# PIC32MK.net
KiCad netlist of a schematic drawn in Altium Designer
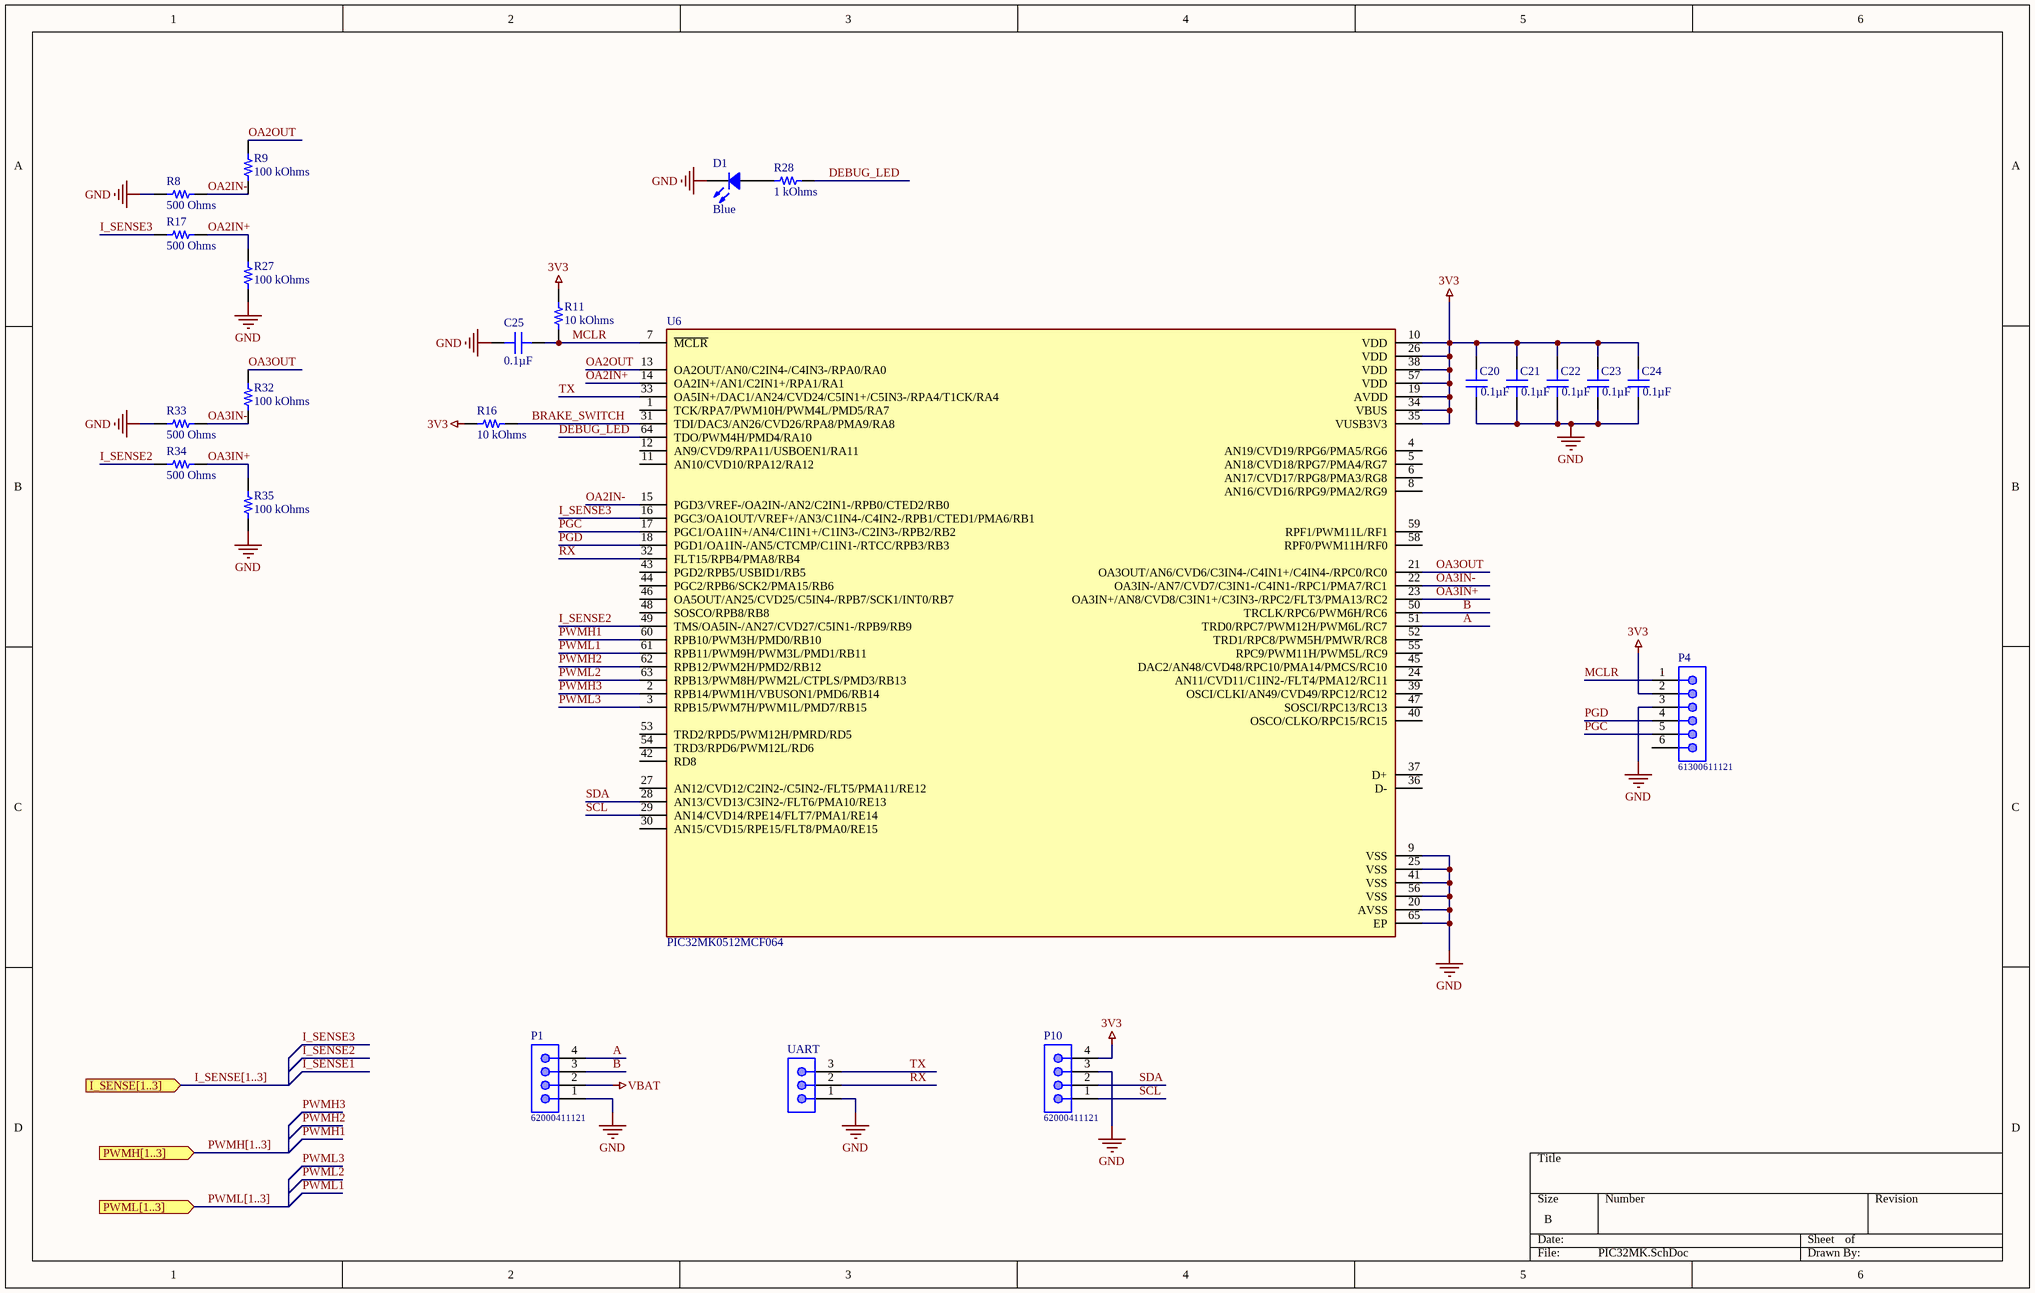
[diagram p0: PIC32MK.SchDoc]

(export (version "E")
  (design (tool "Eeschema 10.0.6"))
  (components
    (comp (ref "C20")
      (value "0.1µF")
      (footprint "CAP 0603_1608")
      (description "CAP CER 0.1UF 100V 0603 EPOXY")
      (fields
        (field (name "PART NUMBER") "GCG188R92A104KA03D")
        (field (name "MANUFACTURER") "Murata Electronics")
      )
      (libsource (lib "Celestial Altium Library - altium_library") (part "Capacitor"))
    )
    (comp (ref "C21")
      (value "0.1µF")
      (footprint "CAP 0603_1608")
      (description "CAP CER 0.1UF 100V 0603 EPOXY")
      (fields
        (field (name "PART NUMBER") "GCG188R92A104KA03D")
        (field (name "MANUFACTURER") "Murata Electronics")
      )
      (libsource (lib "Celestial Altium Library - altium_library") (part "Capacitor"))
    )
    (comp (ref "C22")
      (value "0.1µF")
      (footprint "CAP 0603_1608")
      (description "CAP CER 0.1UF 100V 0603 EPOXY")
      (fields
        (field (name "PART NUMBER") "GCG188R92A104KA03D")
        (field (name "MANUFACTURER") "Murata Electronics")
      )
      (libsource (lib "Celestial Altium Library - altium_library") (part "Capacitor"))
    )
    (comp (ref "C23")
      (value "0.1µF")
      (footprint "CAP 0603_1608")
      (description "CAP CER 0.1UF 100V 0603 EPOXY")
      (fields
        (field (name "PART NUMBER") "GCG188R92A104KA03D")
        (field (name "MANUFACTURER") "Murata Electronics")
      )
      (libsource (lib "Celestial Altium Library - altium_library") (part "Capacitor"))
    )
    (comp (ref "C24")
      (value "0.1µF")
      (footprint "CAP 0603_1608")
      (description "CAP CER 0.1UF 100V 0603 EPOXY")
      (fields
        (field (name "PART NUMBER") "GCG188R92A104KA03D")
        (field (name "MANUFACTURER") "Murata Electronics")
      )
      (libsource (lib "Celestial Altium Library - altium_library") (part "Capacitor"))
    )
    (comp (ref "C25")
      (value "0.1µF")
      (footprint "CAP 0603_1608")
      (description "CAP CER 0.1UF 100V 0603 EPOXY")
      (fields
        (field (name "PART NUMBER") "GCG188R92A104KA03D")
        (field (name "MANUFACTURER") "Murata Electronics")
      )
      (libsource (lib "Celestial Altium Library - altium_library") (part "Capacitor"))
    )
    (comp (ref "D1")
      (value "Blue")
      (footprint "LED 0603_1608 GREEN")
      (description "Blue LED")
      (fields (field (name "PART NUMBER") "XZCDGK53W-8VF") (field (name "MANUFACTURER") "SunLED"))
      (libsource (lib "Celestial Altium Library - altium_library") (part "LED"))
    )
    (comp (ref "P1")
      (value "62000411121")
      (footprint "62000411121")
      (description "WR-PHD Pin Header, THT, pitch 2mm, Single Row, Vertical, 4p")
      (fields (field (name "MANUFACTURER") "Wurth Elektronik"))
      (libsource (lib "Altium_WR-PHD") (part "62000411121"))
    )
    (comp (ref "P4")
      (value "61300611121")
      (footprint "61300611121")
      (description "WR-PHD Pin Header, THT, pitch 2.54mm, Single Row, Vertical, 6p")
      (fields (field (name "MANUFACTURER") "Wurth Elektronik"))
      (libsource (lib "Altium_WR-PHD") (part "61300611121"))
    )
    (comp (ref "P10")
      (value "62000411121")
      (footprint "62000411121")
      (description "WR-PHD Pin Header, THT, pitch 2mm, Single Row, Vertical, 4p")
      (fields (field (name "MANUFACTURER") "Wurth Elektronik"))
      (libsource (lib "Altium_WR-PHD") (part "62000411121"))
    )
    (comp (ref "R8")
      (value "500 Ohms")
      (footprint "RES 0603_1608")
      (description "RES SMD 500 OHM 0.05% 1/10W 0603")
      (fields (field (name "PART NUMBER") "TNPU0603500RAZEN00") (field (name "MANUFACTURER") "Vishay Dale"))
      (libsource (lib "Celestial Altium Library - altium_library") (part "Resistor"))
    )
    (comp (ref "R9")
      (value "100 kOhms")
      (footprint "RES 0603_1608")
      (description "RES SMD 100K OHM 1% 1/4W 0603")
      (fields (field (name "PART NUMBER") "RCA0603100KFKEAHP") (field (name "MANUFACTURER") "Vishay Dale"))
      (libsource (lib "Celestial Altium Library - altium_library") (part "Resistor"))
    )
    (comp (ref "R11")
      (value "10 kOhms")
      (footprint "RES 0603_1608")
      (description "RES 10K OHM 0.1% 1/16W 0603")
      (fields
        (field (name "PART NUMBER") "RNCS0603BKE10K0")
        (field (name "MANUFACTURER") "Stackpole Electronics Inc")
      )
      (libsource (lib "Celestial Altium Library - altium_library") (part "Resistor"))
    )
    (comp (ref "R16")
      (value "10 kOhms")
      (footprint "RES 0603_1608")
      (description "RES 10K OHM 0.1% 1/16W 0603")
      (fields
        (field (name "PART NUMBER") "RNCS0603BKE10K0")
        (field (name "MANUFACTURER") "Stackpole Electronics Inc")
      )
      (libsource (lib "Celestial Altium Library - altium_library") (part "Resistor"))
    )
    (comp (ref "R17")
      (value "500 Ohms")
      (footprint "RES 0603_1608")
      (description "RES SMD 500 OHM 0.05% 1/10W 0603")
      (fields (field (name "PART NUMBER") "TNPU0603500RAZEN00") (field (name "MANUFACTURER") "Vishay Dale"))
      (libsource (lib "Celestial Altium Library - altium_library") (part "Resistor"))
    )
    (comp (ref "R27")
      (value "100 kOhms")
      (footprint "RES 0603_1608")
      (description "RES SMD 100K OHM 1% 1/4W 0603")
      (fields (field (name "PART NUMBER") "RCA0603100KFKEAHP") (field (name "MANUFACTURER") "Vishay Dale"))
      (libsource (lib "Celestial Altium Library - altium_library") (part "Resistor"))
    )
    (comp (ref "R28")
      (value "1 kOhms")
      (footprint "RES 0603_1608")
      (description "RES 1K OHM 0.5% 1/10W 0603")
      (fields
        (field (name "PART NUMBER") "RNCF0603DTE1K00")
        (field (name "MANUFACTURER") "Stackpole Electronics Inc")
      )
      (libsource (lib "Celestial Altium Library - altium_library") (part "Resistor"))
    )
    (comp (ref "R32")
      (value "100 kOhms")
      (footprint "RES 0603_1608")
      (description "RES SMD 100K OHM 1% 1/4W 0603")
      (fields (field (name "PART NUMBER") "RCA0603100KFKEAHP") (field (name "MANUFACTURER") "Vishay Dale"))
      (libsource (lib "Celestial Altium Library - altium_library") (part "Resistor"))
    )
    (comp (ref "R33")
      (value "500 Ohms")
      (footprint "RES 0603_1608")
      (description "RES SMD 500 OHM 0.05% 1/10W 0603")
      (fields (field (name "PART NUMBER") "TNPU0603500RAZEN00") (field (name "MANUFACTURER") "Vishay Dale"))
      (libsource (lib "Celestial Altium Library - altium_library") (part "Resistor"))
    )
    (comp (ref "R34")
      (value "500 Ohms")
      (footprint "RES 0603_1608")
      (description "RES SMD 500 OHM 0.05% 1/10W 0603")
      (fields (field (name "PART NUMBER") "TNPU0603500RAZEN00") (field (name "MANUFACTURER") "Vishay Dale"))
      (libsource (lib "Celestial Altium Library - altium_library") (part "Resistor"))
    )
    (comp (ref "R35")
      (value "100 kOhms")
      (footprint "RES 0603_1608")
      (description "RES SMD 100K OHM 1% 1/4W 0603")
      (fields (field (name "PART NUMBER") "RCA0603100KFKEAHP") (field (name "MANUFACTURER") "Vishay Dale"))
      (libsource (lib "Celestial Altium Library - altium_library") (part "Resistor"))
    )
    (comp (ref "U6")
      (value "PIC32MK0512MCF064")
      (footprint "QFN50P900X900X100-65N")
      (description "PIC32MK Microcontroller IC 32-Bit 120MHz 1MB _1M x 8_ FLASH 64-TQFP _10x10_")
      (fields
        (field (name "MP") "PIC32MK1024MCF064-I/PT")
        (field (name "DIGI-KEY_PART_NUMBER") "PIC32MK1024MCF064-I/PT-ND")
      )
      (libsource (lib "IC") (part "PIC32MK0512MCF064"))
    )
    (comp (ref "UART")
      (value "3 pin 2mm JST Male")
      (footprint "3pin - 2mm header")
      (libsource (lib "IC") (part "3 pin 2mm JST Male"))
    )
  )
  (nets
    (net (code "1") (name "/A") (class "Default")
      (node (ref "P1") (pin "4") (pinfunction "4_4") (pintype "passive"))
      (node (ref "U6") (pin "51") (pinfunction "TRD0/RPC7/PWM12H/PWM6L/RC7_51") (pintype "passive"))
    )
    (net (code "2") (name "/B") (class "Default")
      (node (ref "P1") (pin "3") (pinfunction "3_3") (pintype "passive"))
      (node (ref "U6") (pin "50") (pinfunction "TRCLK/RPC6/PWM6H/RC6_50") (pintype "passive"))
    )
    (net (code "3") (name "/BRAKE_SWITCH") (class "Default")
      (node (ref "R16") (pin "1") (pinfunction "1_1") (pintype "passive"))
      (node (ref "U6") (pin "31") (pinfunction "TDI/DAC3/AN26/CVD26/RPA8/PMA9/RA8_31") (pintype "passive"))
    )
    (net (code "4") (name "/DEBUG_LED") (class "Default")
      (node (ref "R28") (pin "1") (pinfunction "1_1") (pintype "passive"))
      (node (ref "U6") (pin "64") (pinfunction "TDO/PWM4H/PMD4/RA10_64") (pintype "passive"))
    )
    (net (code "6") (name "/I_SENSE2") (class "Default")
      (node (ref "R34") (pin "1") (pinfunction "1_1") (pintype "passive"))
      (node (ref "U6") (pin "49") (pinfunction "TMS/OA5IN-/AN27/CVD27/C5IN1-/RPB9/RB9_49") (pintype "passive"))
    )
    (net (code "7") (name "/I_SENSE3") (class "Default")
      (node (ref "R17") (pin "1") (pinfunction "1_1") (pintype "passive"))
      (node (ref "U6") (pin "16") (pinfunction "PGC3/OA1OUT/VREF+/AN3/C1IN4-/C4IN2-/RPB1/CTED1/PMA6/RB1_16") (pintype "passive"))
    )
    (net (code "9") (name "/MCLR") (class "Default")
      (node (ref "C25") (pin "1") (pinfunction "1_1") (pintype "passive"))
      (node (ref "P4") (pin "1") (pinfunction "1_1") (pintype "passive"))
      (node (ref "R11") (pin "1") (pinfunction "1_1") (pintype "passive"))
      (node (ref "U6") (pin "7") (pinfunction "~{MCLR}_7") (pintype "passive"))
    )
    (net (code "10") (name "/OA2IN+") (class "Default")
      (node (ref "R17") (pin "2") (pinfunction "2_2") (pintype "passive"))
      (node (ref "R27") (pin "2") (pinfunction "2_2") (pintype "passive"))
      (node (ref "U6") (pin "14") (pinfunction "OA2IN+/AN1/C2IN1+/RPA1/RA1_14") (pintype "passive"))
    )
    (net (code "11") (name "/OA2IN-") (class "Default")
      (node (ref "R8") (pin "2") (pinfunction "2_2") (pintype "passive"))
      (node (ref "R9") (pin "1") (pinfunction "1_1") (pintype "passive"))
      (node (ref "U6") (pin "15") (pinfunction "PGD3/VREF-/OA2IN-/AN2/C2IN1-/RPB0/CTED2/RB0_15") (pintype "passive"))
    )
    (net (code "12") (name "/OA2OUT") (class "Default")
      (node (ref "R9") (pin "2") (pinfunction "2_2") (pintype "passive"))
      (node (ref "U6") (pin "13") (pinfunction "OA2OUT/AN0/C2IN4-/C4IN3-/RPA0/RA0_13") (pintype "passive"))
    )
    (net (code "13") (name "/OA3IN+") (class "Default")
      (node (ref "R34") (pin "2") (pinfunction "2_2") (pintype "passive"))
      (node (ref "R35") (pin "2") (pinfunction "2_2") (pintype "passive"))
      (node (ref "U6") (pin "23") (pinfunction "OA3IN+/AN8/CVD8/C3IN1+/C3IN3-/RPC2/FLT3/PMA13/RC2_23") (pintype "passive"))
    )
    (net (code "14") (name "/OA3IN-") (class "Default")
      (node (ref "R32") (pin "1") (pinfunction "1_1") (pintype "passive"))
      (node (ref "R33") (pin "2") (pinfunction "2_2") (pintype "passive"))
      (node (ref "U6") (pin "22") (pinfunction "OA3IN-/AN7/CVD7/C3IN1-/C4IN1-/RPC1/PMA7/RC1_22") (pintype "passive"))
    )
    (net (code "15") (name "/OA3OUT") (class "Default")
      (node (ref "R32") (pin "2") (pinfunction "2_2") (pintype "passive"))
      (node (ref "U6") (pin "21") (pinfunction "OA3OUT/AN6/CVD6/C3IN4-/C4IN1+/C4IN4-/RPC0/RC0_21") (pintype "passive"))
    )
    (net (code "16") (name "/PGC") (class "Default")
      (node (ref "P4") (pin "5") (pinfunction "5_5") (pintype "passive"))
      (node (ref "U6") (pin "17") (pinfunction "PGC1/OA1IN+/AN4/C1IN1+/C1IN3-/C2IN3-/RPB2/RB2_17") (pintype "passive"))
    )
    (net (code "17") (name "/PGD") (class "Default")
      (node (ref "P4") (pin "4") (pinfunction "4_4") (pintype "passive"))
      (node (ref "U6") (pin "18") (pinfunction "PGD1/OA1IN-/AN5/CTCMP/C1IN1-/RTCC/RPB3/RB3_18") (pintype "passive"))
    )
    (net (code "18") (name "/PWMH1") (class "Default")
      (node (ref "U6") (pin "60") (pinfunction "RPB10/PWM3H/PMD0/RB10_60") (pintype "passive"))
    )
    (net (code "19") (name "/PWMH2") (class "Default")
      (node (ref "U6") (pin "62") (pinfunction "RPB12/PWM2H/PMD2/RB12_62") (pintype "passive"))
    )
    (net (code "20") (name "/PWMH3") (class "Default")
      (node (ref "U6") (pin "2") (pinfunction "RPB14/PWM1H/VBUSON1/PMD6/RB14_2") (pintype "passive"))
    )
    (net (code "22") (name "/PWML1") (class "Default")
      (node (ref "U6") (pin "61") (pinfunction "RPB11/PWM9H/PWM3L/PMD1/RB11_61") (pintype "passive"))
    )
    (net (code "23") (name "/PWML2") (class "Default")
      (node (ref "U6") (pin "63") (pinfunction "RPB13/PWM8H/PWM2L/CTPLS/PMD3/RB13_63") (pintype "passive"))
    )
    (net (code "24") (name "/PWML3") (class "Default")
      (node (ref "U6") (pin "3") (pinfunction "RPB15/PWM7H/PWM1L/PMD7/RB15_3") (pintype "passive"))
    )
    (net (code "26") (name "/RX") (class "Default")
      (node (ref "U6") (pin "32") (pinfunction "FLT15/RPB4/PMA8/RB4_32") (pintype "passive"))
      (node (ref "UART") (pin "2") (pinfunction "2_2") (pintype "passive"))
    )
    (net (code "27") (name "/SCL") (class "Default")
      (node (ref "P10") (pin "1") (pinfunction "1_1") (pintype "passive"))
      (node (ref "U6") (pin "29") (pinfunction "AN14/CVD14/RPE14/FLT7/PMA1/RE14_29") (pintype "passive"))
    )
    (net (code "28") (name "/SDA") (class "Default")
      (node (ref "P10") (pin "2") (pinfunction "2_2") (pintype "passive"))
      (node (ref "U6") (pin "28") (pinfunction "AN13/CVD13/C3IN2-/FLT6/PMA10/RE13_28") (pintype "passive"))
    )
    (net (code "29") (name "/TX") (class "Default")
      (node (ref "U6") (pin "33") (pinfunction "OA5IN+/DAC1/AN24/CVD24/C5IN1+/C5IN3-/RPA4/T1CK/RA4_33") (pintype "passive"))
      (node (ref "UART") (pin "3") (pinfunction "3_3") (pintype "passive"))
    )
    (net (code "30") (name "3V3") (class "Default")
      (node (ref "C20") (pin "1") (pinfunction "1_1") (pintype "passive"))
      (node (ref "C21") (pin "1") (pinfunction "1_1") (pintype "passive"))
      (node (ref "C22") (pin "1") (pinfunction "1_1") (pintype "passive"))
      (node (ref "C23") (pin "1") (pinfunction "1_1") (pintype "passive"))
      (node (ref "C24") (pin "1") (pinfunction "1_1") (pintype "passive"))
      (node (ref "P10") (pin "4") (pinfunction "4_4") (pintype "passive"))
      (node (ref "P4") (pin "2") (pinfunction "2_2") (pintype "passive"))
      (node (ref "R11") (pin "2") (pinfunction "2_2") (pintype "passive"))
      (node (ref "R16") (pin "2") (pinfunction "2_2") (pintype "passive"))
      (node (ref "U6") (pin "10") (pinfunction "VDD_10") (pintype "power_in"))
      (node (ref "U6") (pin "19") (pinfunction "AVDD_19") (pintype "power_in"))
      (node (ref "U6") (pin "26") (pinfunction "VDD_26") (pintype "power_in"))
      (node (ref "U6") (pin "34") (pinfunction "VBUS_34") (pintype "power_in"))
      (node (ref "U6") (pin "35") (pinfunction "VUSB3V3_35") (pintype "passive"))
      (node (ref "U6") (pin "38") (pinfunction "VDD_38") (pintype "power_in"))
      (node (ref "U6") (pin "57") (pinfunction "VDD_57") (pintype "power_in"))
    )
    (net (code "31") (name "GND") (class "Default")
      (node (ref "C20") (pin "2") (pinfunction "2_2") (pintype "passive"))
      (node (ref "C21") (pin "2") (pinfunction "2_2") (pintype "passive"))
      (node (ref "C22") (pin "2") (pinfunction "2_2") (pintype "passive"))
      (node (ref "C23") (pin "2") (pinfunction "2_2") (pintype "passive"))
      (node (ref "C24") (pin "2") (pinfunction "2_2") (pintype "passive"))
      (node (ref "C25") (pin "2") (pinfunction "2_2") (pintype "passive"))
      (node (ref "D1") (pin "2") (pinfunction "2_2") (pintype "passive"))
      (node (ref "P1") (pin "1") (pinfunction "1_1") (pintype "passive"))
      (node (ref "P10") (pin "3") (pinfunction "3_3") (pintype "passive"))
      (node (ref "P4") (pin "3") (pinfunction "3_3") (pintype "passive"))
      (node (ref "R27") (pin "1") (pinfunction "1_1") (pintype "passive"))
      (node (ref "R33") (pin "1") (pinfunction "1_1") (pintype "passive"))
      (node (ref "R35") (pin "1") (pinfunction "1_1") (pintype "passive"))
      (node (ref "R8") (pin "1") (pinfunction "1_1") (pintype "passive"))
      (node (ref "U6") (pin "20") (pinfunction "AVSS_20") (pintype "power_in"))
      (node (ref "U6") (pin "25") (pinfunction "VSS_25") (pintype "power_in"))
      (node (ref "U6") (pin "41") (pinfunction "VSS_41") (pintype "power_in"))
      (node (ref "U6") (pin "56") (pinfunction "VSS_56") (pintype "power_in"))
      (node (ref "U6") (pin "65") (pinfunction "EP_65") (pintype "power_in"))
      (node (ref "U6") (pin "9") (pinfunction "VSS_9") (pintype "power_in"))
      (node (ref "UART") (pin "1") (pinfunction "1_1") (pintype "passive"))
    )
    (net (code "32") (name "Net-(D1-Pad1)") (class "Default")
      (node (ref "D1") (pin "1") (pinfunction "1_1") (pintype "passive"))
      (node (ref "R28") (pin "2") (pinfunction "2_2") (pintype "passive"))
    )
    (net (code "33") (name "VBAT") (class "Default")
      (node (ref "P1") (pin "2") (pinfunction "2_2") (pintype "passive"))
    )
    (net (code "34") (name "unconnected-(P4-Pad6)") (class "Default")
      (node (ref "P4") (pin "6") (pinfunction "6_6") (pintype "passive"))
    )
    (net (code "35") (name "unconnected-(U6-AN9{slash}CVD9{slash}RPA11{slash}USBOEN1{slash}RA11-Pad12)") (class "Default")
      (node (ref "U6") (pin "12") (pinfunction "AN9/CVD9/RPA11/USBOEN1/RA11_12") (pintype "passive"))
    )
    (net (code "36") (name "unconnected-(U6-AN10{slash}CVD10{slash}RPA12{slash}RA12-Pad11)") (class "Default")
      (node (ref "U6") (pin "11") (pinfunction "AN10/CVD10/RPA12/RA12_11") (pintype "passive"))
    )
    (net (code "37") (name "unconnected-(U6-AN11{slash}CVD11{slash}C1IN2-{slash}FLT4{slash}PMA12{slash}RC11-Pad24)") (class "Default")
      (node (ref "U6") (pin "24") (pinfunction "AN11/CVD11/C1IN2-/FLT4/PMA12/RC11_24") (pintype "passive"))
    )
    (net (code "38") (name "unconnected-(U6-AN12{slash}CVD12{slash}C2IN2-{slash}C5IN2-{slash}FLT5{slash}PMA11{slash}RE12-Pad27)") (class "Default")
      (node (ref "U6") (pin "27") (pinfunction "AN12/CVD12/C2IN2-/C5IN2-/FLT5/PMA11/RE12_27") (pintype "passive"))
    )
    (net (code "39") (name "unconnected-(U6-AN15{slash}CVD15{slash}RPE15{slash}FLT8{slash}PMA0{slash}RE15-Pad30)") (class "Default")
      (node (ref "U6") (pin "30") (pinfunction "AN15/CVD15/RPE15/FLT8/PMA0/RE15_30") (pintype "passive"))
    )
    (net (code "40") (name "unconnected-(U6-AN16{slash}CVD16{slash}RPG9{slash}PMA2{slash}RG9-Pad8)") (class "Default")
      (node (ref "U6") (pin "8") (pinfunction "AN16/CVD16/RPG9/PMA2/RG9_8") (pintype "passive"))
    )
    (net (code "41") (name "unconnected-(U6-AN17{slash}CVD17{slash}RPG8{slash}PMA3{slash}RG8-Pad6)") (class "Default")
      (node (ref "U6") (pin "6") (pinfunction "AN17/CVD17/RPG8/PMA3/RG8_6") (pintype "passive"))
    )
    (net (code "42") (name "unconnected-(U6-AN18{slash}CVD18{slash}RPG7{slash}PMA4{slash}RG7-Pad5)") (class "Default")
      (node (ref "U6") (pin "5") (pinfunction "AN18/CVD18/RPG7/PMA4/RG7_5") (pintype "passive"))
    )
    (net (code "43") (name "unconnected-(U6-AN19{slash}CVD19{slash}RPG6{slash}PMA5{slash}RG6-Pad4)") (class "Default")
      (node (ref "U6") (pin "4") (pinfunction "AN19/CVD19/RPG6/PMA5/RG6_4") (pintype "passive"))
    )
    (net (code "44") (name "unconnected-(U6-D+-Pad37)") (class "Default")
      (node (ref "U6") (pin "37") (pinfunction "D+_37") (pintype "passive"))
    )
    (net (code "45") (name "unconnected-(U6-D--Pad36)") (class "Default")
      (node (ref "U6") (pin "36") (pinfunction "D-_36") (pintype "passive"))
    )
    (net (code "46") (name "unconnected-(U6-DAC2{slash}AN48{slash}CVD48{slash}RPC10{slash}PMA14{slash}PMCS{slash}RC10-Pad45)") (class "Default")
      (node (ref "U6") (pin "45") (pinfunction "DAC2/AN48/CVD48/RPC10/PMA14/PMCS/RC10_45") (pintype "passive"))
    )
    (net (code "47") (name "unconnected-(U6-OA5OUT{slash}AN25{slash}CVD25{slash}C5IN4-{slash}RPB7{slash}SCK1{slash}INT0{slash}RB7-Pad46)") (class "Default")
      (node (ref "U6") (pin "46") (pinfunction "OA5OUT/AN25/CVD25/C5IN4-/RPB7/SCK1/INT0/RB7_46") (pintype "passive"))
    )
    (net (code "48") (name "unconnected-(U6-OSCI{slash}CLKI{slash}AN49{slash}CVD49{slash}RPC12{slash}RC12-Pad39)") (class "Default")
      (node (ref "U6") (pin "39") (pinfunction "OSCI/CLKI/AN49/CVD49/RPC12/RC12_39") (pintype "passive"))
    )
    (net (code "49") (name "unconnected-(U6-OSCO{slash}CLKO{slash}RPC15{slash}RC15-Pad40)") (class "Default")
      (node (ref "U6") (pin "40") (pinfunction "OSCO/CLKO/RPC15/RC15_40") (pintype "passive"))
    )
    (net (code "50") (name "unconnected-(U6-PGC2{slash}RPB6{slash}SCK2{slash}PMA15{slash}RB6-Pad44)") (class "Default")
      (node (ref "U6") (pin "44") (pinfunction "PGC2/RPB6/SCK2/PMA15/RB6_44") (pintype "passive"))
    )
    (net (code "51") (name "unconnected-(U6-PGD2{slash}RPB5{slash}USBID1{slash}RB5-Pad43)") (class "Default")
      (node (ref "U6") (pin "43") (pinfunction "PGD2/RPB5/USBID1/RB5_43") (pintype "passive"))
    )
    (net (code "52") (name "unconnected-(U6-RD8-Pad42)") (class "Default")
      (node (ref "U6") (pin "42") (pinfunction "RD8_42") (pintype "passive"))
    )
    (net (code "53") (name "unconnected-(U6-RPC9{slash}PWM11H{slash}PWM5L{slash}RC9-Pad55)") (class "Default")
      (node (ref "U6") (pin "55") (pinfunction "RPC9/PWM11H/PWM5L/RC9_55") (pintype "passive"))
    )
    (net (code "54") (name "unconnected-(U6-RPF0{slash}PWM11H{slash}RF0-Pad58)") (class "Default")
      (node (ref "U6") (pin "58") (pinfunction "RPF0/PWM11H/RF0_58") (pintype "passive"))
    )
    (net (code "55") (name "unconnected-(U6-RPF1{slash}PWM11L{slash}RF1-Pad59)") (class "Default")
      (node (ref "U6") (pin "59") (pinfunction "RPF1/PWM11L/RF1_59") (pintype "passive"))
    )
    (net (code "56") (name "unconnected-(U6-SOSCI{slash}RPC13{slash}RC13-Pad47)") (class "Default")
      (node (ref "U6") (pin "47") (pinfunction "SOSCI/RPC13/RC13_47") (pintype "passive"))
    )
    (net (code "57") (name "unconnected-(U6-SOSCO{slash}RPB8{slash}RB8-Pad48)") (class "Default")
      (node (ref "U6") (pin "48") (pinfunction "SOSCO/RPB8/RB8_48") (pintype "passive"))
    )
    (net (code "58") (name "unconnected-(U6-TCK{slash}RPA7{slash}PWM10H{slash}PWM4L{slash}PMD5{slash}RA7-Pad1)") (class "Default")
      (node (ref "U6") (pin "1") (pinfunction "TCK/RPA7/PWM10H/PWM4L/PMD5/RA7_1") (pintype "passive"))
    )
    (net (code "59") (name "unconnected-(U6-TRD1{slash}RPC8{slash}PWM5H{slash}PMWR{slash}RC8-Pad52)") (class "Default")
      (node (ref "U6") (pin "52") (pinfunction "TRD1/RPC8/PWM5H/PMWR/RC8_52") (pintype "passive"))
    )
    (net (code "60") (name "unconnected-(U6-TRD2{slash}RPD5{slash}PWM12H{slash}PMRD{slash}RD5-Pad53)") (class "Default")
      (node (ref "U6") (pin "53") (pinfunction "TRD2/RPD5/PWM12H/PMRD/RD5_53") (pintype "passive"))
    )
    (net (code "61") (name "unconnected-(U6-TRD3{slash}RPD6{slash}PWM12L{slash}RD6-Pad54)") (class "Default")
      (node (ref "U6") (pin "54") (pinfunction "TRD3/RPD6/PWM12L/RD6_54") (pintype "passive"))
    )
  )
)
